# uC.net
KiCad netlist of a schematic drawn in Altium Designer
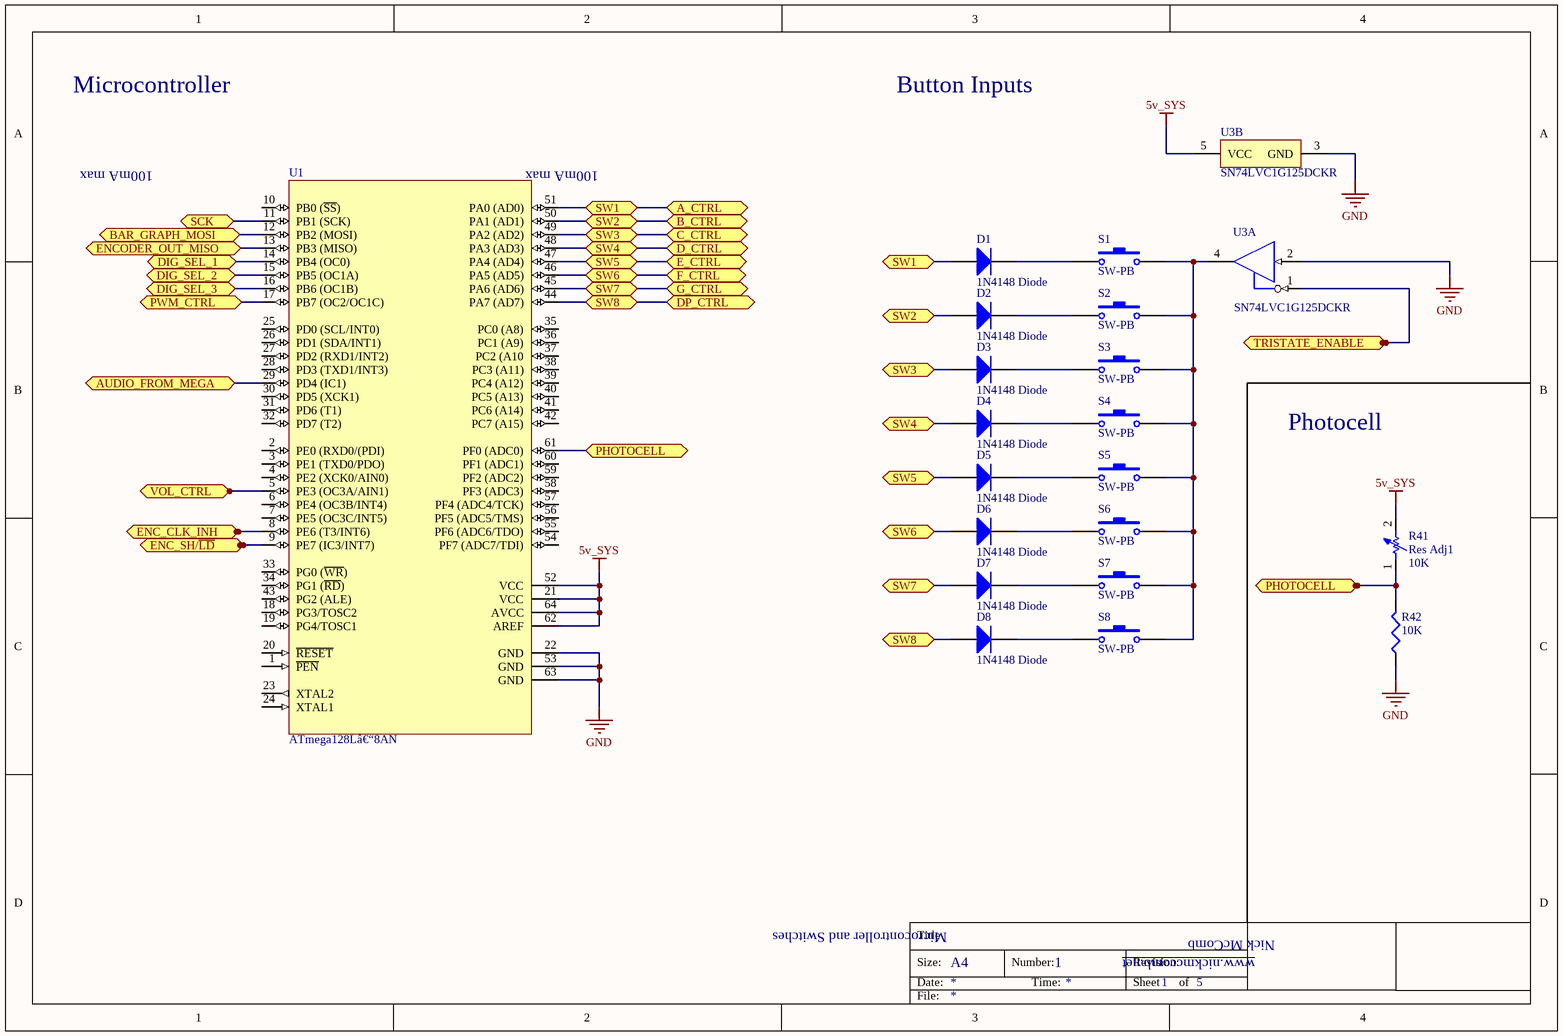
[diagram p0: uC.SchDoc]

(export (version "E")
  (design (tool "Eeschema 10.0.6"))
  (components
    (comp (ref "D1")
      (value "1N4148 Diode")
      (footprint "S01575 Diode")
      (description "Diode")
      (libsource (lib "lab2") (part "Diode"))
    )
    (comp (ref "D2")
      (value "1N4148 Diode")
      (footprint "S01575 Diode")
      (description "Diode")
      (libsource (lib "lab2") (part "Diode"))
    )
    (comp (ref "D3")
      (value "1N4148 Diode")
      (footprint "S01575 Diode")
      (description "Diode")
      (libsource (lib "lab2") (part "Diode"))
    )
    (comp (ref "D4")
      (value "1N4148 Diode")
      (footprint "S01575 Diode")
      (description "Diode")
      (libsource (lib "lab2") (part "Diode"))
    )
    (comp (ref "D5")
      (value "1N4148 Diode")
      (footprint "S01575 Diode")
      (description "Diode")
      (libsource (lib "lab2") (part "Diode"))
    )
    (comp (ref "D6")
      (value "1N4148 Diode")
      (footprint "S01575 Diode")
      (description "Diode")
      (libsource (lib "lab2") (part "Diode"))
    )
    (comp (ref "D7")
      (value "1N4148 Diode")
      (footprint "S01575 Diode")
      (description "Diode")
      (libsource (lib "lab2") (part "Diode"))
    )
    (comp (ref "D8")
      (value "1N4148 Diode")
      (footprint "S01575 Diode")
      (description "Diode")
      (libsource (lib "lab2") (part "Diode"))
    )
    (comp (ref "R41")
      (value "Res Adj1")
      (footprint "LOG POT")
      (description "Variable Resistor")
      (fields (field (name "ALTIUM_VALUE") "10K"))
      (libsource (lib "lab2") (part "Res Adj1"))
    )
    (comp (ref "R42")
      (value "10K")
      (footprint "J1-0603")
      (description "Resistor")
      (fields (field (name "PUBLISHER") "Altium Limited"))
      (libsource (lib "lab2") (part "Res3"))
    )
    (comp (ref "S1")
      (value "SW-PB")
      (footprint "SW-PB")
      (description "Switch")
      (libsource (lib "lab2") (part "SW-PB"))
    )
    (comp (ref "S2")
      (value "SW-PB")
      (footprint "SW-PB")
      (description "Switch")
      (libsource (lib "lab2") (part "SW-PB"))
    )
    (comp (ref "S3")
      (value "SW-PB")
      (footprint "SW-PB")
      (description "Switch")
      (libsource (lib "lab2") (part "SW-PB"))
    )
    (comp (ref "S4")
      (value "SW-PB")
      (footprint "SW-PB")
      (description "Switch")
      (libsource (lib "lab2") (part "SW-PB"))
    )
    (comp (ref "S5")
      (value "SW-PB")
      (footprint "SW-PB")
      (description "Switch")
      (libsource (lib "lab2") (part "SW-PB"))
    )
    (comp (ref "S6")
      (value "SW-PB")
      (footprint "SW-PB")
      (description "Switch")
      (libsource (lib "lab2") (part "SW-PB"))
    )
    (comp (ref "S7")
      (value "SW-PB")
      (footprint "SW-PB")
      (description "Switch")
      (libsource (lib "lab2") (part "SW-PB"))
    )
    (comp (ref "S8")
      (value "SW-PB")
      (footprint "SW-PB")
      (description "Switch")
      (libsource (lib "lab2") (part "SW-PB"))
    )
    (comp (ref "U1")
      (value "ATmega128Lâ€“8AN")
      (footprint "64A_M")
      (libsource (lib "Altium Content Vault") (part "MC-8B-AT64-SQ64"))
    )
    (comp (ref "U3")
      (value "SN74LVC1G125DCKR")
      (footprint "DCK0005A_M")
      (description "Single Bus Buffer Gate With 3-State Outputs, DCK0005A, LARGE T&R")
      (fields
        (field (name "GENERIC PART NUMBER") "SN74LVC1G125")
        (field (name "MANUFACTURER") "Texas Instruments")
      )
      (libsource (lib "Altium Content Vault") (part "TI-SN74AXXXX1X125-5"))
    )
  )
  (nets
    (net (code "1") (name "/AUDIO_FROM_MEGA") (class "Default")
      (node (ref "U1") (pin "29") (pinfunction "PD4_(IC1)_29") (pintype "bidirectional"))
    )
    (net (code "2") (name "/A_CTRL") (class "Default")
      (node (ref "D1") (pin "3") (pinfunction "A_3") (pintype "passive"))
      (node (ref "U1") (pin "51") (pinfunction "PA0_(AD0)_51") (pintype "bidirectional"))
    )
    (net (code "3") (name "/BAR_GRAPH_MOSI") (class "Default")
      (node (ref "U1") (pin "12") (pinfunction "PB2_(MOSI)_12") (pintype "bidirectional"))
    )
    (net (code "4") (name "/B_CTRL") (class "Default")
      (node (ref "D2") (pin "3") (pinfunction "A_3") (pintype "passive"))
      (node (ref "U1") (pin "50") (pinfunction "PA1_(AD1)_50") (pintype "bidirectional"))
    )
    (net (code "5") (name "/C_CTRL") (class "Default")
      (node (ref "D3") (pin "3") (pinfunction "A_3") (pintype "passive"))
      (node (ref "U1") (pin "49") (pinfunction "PA2_(AD2)_49") (pintype "bidirectional"))
    )
    (net (code "6") (name "/DIG_SEL_1") (class "Default")
      (node (ref "U1") (pin "14") (pinfunction "PB4_(OC0)_14") (pintype "bidirectional"))
    )
    (net (code "7") (name "/DIG_SEL_2") (class "Default")
      (node (ref "U1") (pin "15") (pinfunction "PB5_(OC1A)_15") (pintype "bidirectional"))
    )
    (net (code "8") (name "/DIG_SEL_3") (class "Default")
      (node (ref "U1") (pin "16") (pinfunction "PB6_(OC1B)_16") (pintype "bidirectional"))
    )
    (net (code "9") (name "/DP_CTRL") (class "Default")
      (node (ref "D8") (pin "3") (pinfunction "A_3") (pintype "passive"))
      (node (ref "U1") (pin "44") (pinfunction "PA7_(AD7)_44") (pintype "bidirectional"))
    )
    (net (code "10") (name "/D_CTRL") (class "Default")
      (node (ref "D4") (pin "3") (pinfunction "A_3") (pintype "passive"))
      (node (ref "U1") (pin "48") (pinfunction "PA3_(AD3)_48") (pintype "bidirectional"))
    )
    (net (code "11") (name "/ENCODER_OUT_MISO") (class "Default")
      (node (ref "U1") (pin "13") (pinfunction "PB3_(MISO)_13") (pintype "bidirectional"))
    )
    (net (code "12") (name "/ENC_CLK_INH") (class "Default")
      (node (ref "U1") (pin "8") (pinfunction "PE6_(T3/INT6)_8") (pintype "bidirectional"))
    )
    (net (code "13") (name "/ENC_SH{slash}~{LD}") (class "Default")
      (node (ref "U1") (pin "9") (pinfunction "PE7_(IC3/INT7)_9") (pintype "bidirectional"))
    )
    (net (code "14") (name "/E_CTRL") (class "Default")
      (node (ref "D5") (pin "3") (pinfunction "A_3") (pintype "passive"))
      (node (ref "U1") (pin "47") (pinfunction "PA4_(AD4)_47") (pintype "bidirectional"))
    )
    (net (code "15") (name "/F_CTRL") (class "Default")
      (node (ref "D6") (pin "3") (pinfunction "A_3") (pintype "passive"))
      (node (ref "U1") (pin "46") (pinfunction "PA5_(AD5)_46") (pintype "bidirectional"))
    )
    (net (code "16") (name "/G_CTRL") (class "Default")
      (node (ref "D7") (pin "3") (pinfunction "A_3") (pintype "passive"))
      (node (ref "U1") (pin "45") (pinfunction "PA6_(AD6)_45") (pintype "bidirectional"))
    )
    (net (code "17") (name "/PHOTOCELL") (class "Default")
      (node (ref "R41") (pin "1") (pinfunction "1_1") (pintype "passive"))
      (node (ref "R42") (pin "2") (pinfunction "2_2") (pintype "passive"))
      (node (ref "U1") (pin "61") (pinfunction "PF0_(ADC0)_61") (pintype "bidirectional"))
    )
    (net (code "18") (name "/PWM_CTRL") (class "Default")
      (node (ref "U1") (pin "17") (pinfunction "PB7_(OC2/OC1C)_17") (pintype "bidirectional"))
    )
    (net (code "19") (name "/SCK") (class "Default")
      (node (ref "U1") (pin "11") (pinfunction "PB1_(SCK)_11") (pintype "bidirectional"))
    )
    (net (code "20") (name "/TRISTATE_ENABLE") (class "Default")
      (node (ref "U3") (pin "1") (pinfunction "~{OE}_1") (pintype "input"))
    )
    (net (code "21") (name "/VOL_CTRL") (class "Default")
      (node (ref "U1") (pin "5") (pinfunction "PE3_(OC3A/AIN1)_5") (pintype "bidirectional"))
    )
    (net (code "22") (name "5v_SYS") (class "Default")
      (node (ref "R41") (pin "2") (pinfunction "2_2") (pintype "passive"))
      (node (ref "U1") (pin "21") (pinfunction "VCC_21") (pintype "power_in"))
      (node (ref "U1") (pin "52") (pinfunction "VCC_52") (pintype "power_in"))
      (node (ref "U1") (pin "62") (pinfunction "AREF_62") (pintype "passive"))
      (node (ref "U1") (pin "64") (pinfunction "AVCC_64") (pintype "power_in"))
      (node (ref "U3") (pin "5") (pinfunction "VCC_5") (pintype "power_in"))
    )
    (net (code "23") (name "GND") (class "Default")
      (node (ref "R42") (pin "1") (pinfunction "1_1") (pintype "passive"))
      (node (ref "U1") (pin "22") (pinfunction "GND_22") (pintype "power_in"))
      (node (ref "U1") (pin "53") (pinfunction "GND_53") (pintype "power_in"))
      (node (ref "U1") (pin "63") (pinfunction "GND_63") (pintype "power_in"))
      (node (ref "U3") (pin "2") (pinfunction "A_2") (pintype "input"))
      (node (ref "U3") (pin "3") (pinfunction "GND_3") (pintype "power_in"))
    )
    (net (code "24") (name "Net-(D1-K)") (class "Default")
      (node (ref "D1") (pin "1") (pinfunction "K_1") (pintype "passive"))
      (node (ref "S1") (pin "1") (pinfunction "1_1") (pintype "passive"))
    )
    (net (code "25") (name "Net-(D2-K)") (class "Default")
      (node (ref "D2") (pin "1") (pinfunction "K_1") (pintype "passive"))
      (node (ref "S2") (pin "1") (pinfunction "1_1") (pintype "passive"))
    )
    (net (code "26") (name "Net-(D3-K)") (class "Default")
      (node (ref "D3") (pin "1") (pinfunction "K_1") (pintype "passive"))
      (node (ref "S3") (pin "1") (pinfunction "1_1") (pintype "passive"))
    )
    (net (code "27") (name "Net-(D4-K)") (class "Default")
      (node (ref "D4") (pin "1") (pinfunction "K_1") (pintype "passive"))
      (node (ref "S4") (pin "1") (pinfunction "1_1") (pintype "passive"))
    )
    (net (code "28") (name "Net-(D5-K)") (class "Default")
      (node (ref "D5") (pin "1") (pinfunction "K_1") (pintype "passive"))
      (node (ref "S5") (pin "1") (pinfunction "1_1") (pintype "passive"))
    )
    (net (code "29") (name "Net-(D6-K)") (class "Default")
      (node (ref "D6") (pin "1") (pinfunction "K_1") (pintype "passive"))
      (node (ref "S6") (pin "1") (pinfunction "1_1") (pintype "passive"))
    )
    (net (code "30") (name "Net-(D7-K)") (class "Default")
      (node (ref "D7") (pin "1") (pinfunction "K_1") (pintype "passive"))
      (node (ref "S7") (pin "1") (pinfunction "1_1") (pintype "passive"))
    )
    (net (code "31") (name "Net-(D8-K)") (class "Default")
      (node (ref "D8") (pin "1") (pinfunction "K_1") (pintype "passive"))
      (node (ref "S8") (pin "1") (pinfunction "1_1") (pintype "passive"))
    )
    (net (code "32") (name "Net-(U3A-Y)") (class "Default")
      (node (ref "S1") (pin "2") (pinfunction "2_2") (pintype "passive"))
      (node (ref "S2") (pin "2") (pinfunction "2_2") (pintype "passive"))
      (node (ref "S3") (pin "2") (pinfunction "2_2") (pintype "passive"))
      (node (ref "S4") (pin "2") (pinfunction "2_2") (pintype "passive"))
      (node (ref "S5") (pin "2") (pinfunction "2_2") (pintype "passive"))
      (node (ref "S6") (pin "2") (pinfunction "2_2") (pintype "passive"))
      (node (ref "S7") (pin "2") (pinfunction "2_2") (pintype "passive"))
      (node (ref "S8") (pin "2") (pinfunction "2_2") (pintype "passive"))
      (node (ref "U3") (pin "4") (pinfunction "Y_4") (pintype "tri_state"))
    )
    (net (code "33") (name "unconnected-(U1-PB0_(~{SS})-Pad10)") (class "Default")
      (node (ref "U1") (pin "10") (pinfunction "PB0_(~{SS})_10") (pintype "bidirectional"))
    )
    (net (code "34") (name "unconnected-(U1-PC0_(A8)-Pad35)") (class "Default")
      (node (ref "U1") (pin "35") (pinfunction "PC0_(A8)_35") (pintype "bidirectional"))
    )
    (net (code "35") (name "unconnected-(U1-PC1_(A9)-Pad36)") (class "Default")
      (node (ref "U1") (pin "36") (pinfunction "PC1_(A9)_36") (pintype "bidirectional"))
    )
    (net (code "36") (name "unconnected-(U1-PC2_(A10-Pad37)") (class "Default")
      (node (ref "U1") (pin "37") (pinfunction "PC2_(A10_37") (pintype "bidirectional"))
    )
    (net (code "37") (name "unconnected-(U1-PC3_(A11)-Pad38)") (class "Default")
      (node (ref "U1") (pin "38") (pinfunction "PC3_(A11)_38") (pintype "bidirectional"))
    )
    (net (code "38") (name "unconnected-(U1-PC4_(A12)-Pad39)") (class "Default")
      (node (ref "U1") (pin "39") (pinfunction "PC4_(A12)_39") (pintype "bidirectional"))
    )
    (net (code "39") (name "unconnected-(U1-PC5_(A13)-Pad40)") (class "Default")
      (node (ref "U1") (pin "40") (pinfunction "PC5_(A13)_40") (pintype "bidirectional"))
    )
    (net (code "40") (name "unconnected-(U1-PC6_(A14)-Pad41)") (class "Default")
      (node (ref "U1") (pin "41") (pinfunction "PC6_(A14)_41") (pintype "bidirectional"))
    )
    (net (code "41") (name "unconnected-(U1-PC7_(A15)-Pad42)") (class "Default")
      (node (ref "U1") (pin "42") (pinfunction "PC7_(A15)_42") (pintype "bidirectional"))
    )
    (net (code "42") (name "unconnected-(U1-PD0_(SCL{slash}INT0)-Pad25)") (class "Default")
      (node (ref "U1") (pin "25") (pinfunction "PD0_(SCL/INT0)_25") (pintype "bidirectional"))
    )
    (net (code "43") (name "unconnected-(U1-PD1_(SDA{slash}INT1)-Pad26)") (class "Default")
      (node (ref "U1") (pin "26") (pinfunction "PD1_(SDA/INT1)_26") (pintype "bidirectional"))
    )
    (net (code "44") (name "unconnected-(U1-PD2_(RXD1{slash}INT2)-Pad27)") (class "Default")
      (node (ref "U1") (pin "27") (pinfunction "PD2_(RXD1/INT2)_27") (pintype "bidirectional"))
    )
    (net (code "45") (name "unconnected-(U1-PD3_(TXD1{slash}INT3)-Pad28)") (class "Default")
      (node (ref "U1") (pin "28") (pinfunction "PD3_(TXD1/INT3)_28") (pintype "bidirectional"))
    )
    (net (code "46") (name "unconnected-(U1-PD5_(XCK1)-Pad30)") (class "Default")
      (node (ref "U1") (pin "30") (pinfunction "PD5_(XCK1)_30") (pintype "bidirectional"))
    )
    (net (code "47") (name "unconnected-(U1-PD6_(T1)-Pad31)") (class "Default")
      (node (ref "U1") (pin "31") (pinfunction "PD6_(T1)_31") (pintype "bidirectional"))
    )
    (net (code "48") (name "unconnected-(U1-PD7_(T2)-Pad32)") (class "Default")
      (node (ref "U1") (pin "32") (pinfunction "PD7_(T2)_32") (pintype "bidirectional"))
    )
    (net (code "49") (name "unconnected-(U1-PE0_(RXD0{slash}(PDI)-Pad2)") (class "Default")
      (node (ref "U1") (pin "2") (pinfunction "PE0_(RXD0/(PDI)_2") (pintype "bidirectional"))
    )
    (net (code "50") (name "unconnected-(U1-PE1_(TXD0{slash}PDO)-Pad3)") (class "Default")
      (node (ref "U1") (pin "3") (pinfunction "PE1_(TXD0/PDO)_3") (pintype "bidirectional"))
    )
    (net (code "51") (name "unconnected-(U1-PE2_(XCK0{slash}AIN0)-Pad4)") (class "Default")
      (node (ref "U1") (pin "4") (pinfunction "PE2_(XCK0/AIN0)_4") (pintype "bidirectional"))
    )
    (net (code "52") (name "unconnected-(U1-PE4_(OC3B{slash}INT4)-Pad6)") (class "Default")
      (node (ref "U1") (pin "6") (pinfunction "PE4_(OC3B/INT4)_6") (pintype "bidirectional"))
    )
    (net (code "53") (name "unconnected-(U1-PE5_(OC3C{slash}INT5)-Pad7)") (class "Default")
      (node (ref "U1") (pin "7") (pinfunction "PE5_(OC3C/INT5)_7") (pintype "bidirectional"))
    )
    (net (code "54") (name "unconnected-(U1-PF1_(ADC1)-Pad60)") (class "Default")
      (node (ref "U1") (pin "60") (pinfunction "PF1_(ADC1)_60") (pintype "bidirectional"))
    )
    (net (code "55") (name "unconnected-(U1-PF2_(ADC2)-Pad59)") (class "Default")
      (node (ref "U1") (pin "59") (pinfunction "PF2_(ADC2)_59") (pintype "bidirectional"))
    )
    (net (code "56") (name "unconnected-(U1-PF3_(ADC3)-Pad58)") (class "Default")
      (node (ref "U1") (pin "58") (pinfunction "PF3_(ADC3)_58") (pintype "bidirectional"))
    )
    (net (code "57") (name "unconnected-(U1-PF4_(ADC4{slash}TCK)-Pad57)") (class "Default")
      (node (ref "U1") (pin "57") (pinfunction "PF4_(ADC4/TCK)_57") (pintype "bidirectional"))
    )
    (net (code "58") (name "unconnected-(U1-PF5_(ADC5{slash}TMS)-Pad56)") (class "Default")
      (node (ref "U1") (pin "56") (pinfunction "PF5_(ADC5/TMS)_56") (pintype "bidirectional"))
    )
    (net (code "59") (name "unconnected-(U1-PF6_(ADC6{slash}TDO)-Pad55)") (class "Default")
      (node (ref "U1") (pin "55") (pinfunction "PF6_(ADC6/TDO)_55") (pintype "bidirectional"))
    )
    (net (code "60") (name "unconnected-(U1-PF7_(ADC7{slash}TDI)-Pad54)") (class "Default")
      (node (ref "U1") (pin "54") (pinfunction "PF7_(ADC7/TDI)_54") (pintype "bidirectional"))
    )
    (net (code "61") (name "unconnected-(U1-PG0_(~{WR})-Pad33)") (class "Default")
      (node (ref "U1") (pin "33") (pinfunction "PG0_(~{WR})_33") (pintype "bidirectional"))
    )
    (net (code "62") (name "unconnected-(U1-PG1_(~{RD})-Pad34)") (class "Default")
      (node (ref "U1") (pin "34") (pinfunction "PG1_(~{RD})_34") (pintype "bidirectional"))
    )
    (net (code "63") (name "unconnected-(U1-PG2_(ALE)-Pad43)") (class "Default")
      (node (ref "U1") (pin "43") (pinfunction "PG2_(ALE)_43") (pintype "bidirectional"))
    )
    (net (code "64") (name "unconnected-(U1-PG3{slash}TOSC2-Pad18)") (class "Default")
      (node (ref "U1") (pin "18") (pinfunction "PG3/TOSC2_18") (pintype "bidirectional"))
    )
    (net (code "65") (name "unconnected-(U1-PG4{slash}TOSC1-Pad19)") (class "Default")
      (node (ref "U1") (pin "19") (pinfunction "PG4/TOSC1_19") (pintype "bidirectional"))
    )
    (net (code "66") (name "unconnected-(U1-XTAL1-Pad24)") (class "Default")
      (node (ref "U1") (pin "24") (pinfunction "XTAL1_24") (pintype "input"))
    )
    (net (code "67") (name "unconnected-(U1-XTAL2-Pad23)") (class "Default")
      (node (ref "U1") (pin "23") (pinfunction "XTAL2_23") (pintype "output"))
    )
    (net (code "68") (name "unconnected-(U1-~{PEN}-Pad1)") (class "Default")
      (node (ref "U1") (pin "1") (pinfunction "~{PEN}_1") (pintype "input"))
    )
    (net (code "69") (name "unconnected-(U1-~{RESET}-Pad20)") (class "Default")
      (node (ref "U1") (pin "20") (pinfunction "~{RESET}_20") (pintype "input"))
    )
  )
)
